# FuzzerFuca.net
KiCad netlist of a schematic drawn in Altium Designer
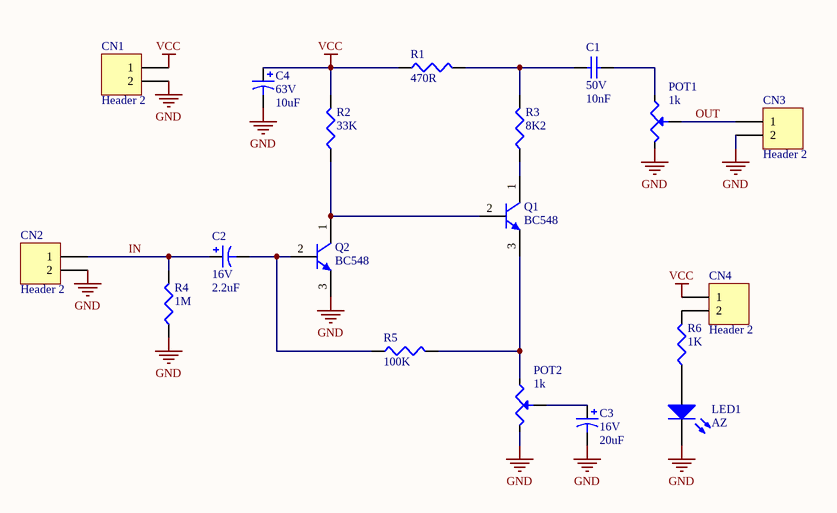
[diagram p0: FuzzerFuca.SchDoc]

(export (version "E")
  (design (tool "Eeschema 10.0.6"))
  (components
    (comp (ref "C1")
      (value "10nF")
      (footprint "CCERAMIC-02I")
      (description "Capacitor (Semiconductor SIM Model)")
      (fields (field (name "TENSÃO") "50V") (field (name "Comment") "Capacitor Cerâmico"))
      (libsource (lib "NavarroCAP") (part "Cap 10nF 50V 0603 X7R 5%"))
    )
    (comp (ref "C2")
      (value "2.2uF")
      (footprint "CPOLRAD5X11")
      (description "Polarized Capacitor")
      (fields (field (name "TENSÃO") "16V") (field (name "Comment") "Capacitor Tântalo"))
      (libsource (lib "NavarroCAP") (part "PCap 2.2uF 16V 1206 LOESR"))
    )
    (comp (ref "C3")
      (value "20uF")
      (footprint "CPOLRAD5X11")
      (description "Polarized Capacitor")
      (fields (field (name "TENSÃO") "16V") (field (name "Comment") "Capacitor Tântalo"))
      (libsource (lib "NavarroCAP") (part "PCap 2.2uF 16V 1206 LOESR"))
    )
    (comp (ref "C4")
      (value "10uF")
      (footprint "CPOLRAD5X11")
      (description "Polarized Capacitor (Radial)")
      (fields (field (name "TENSÃO") "63V") (field (name "Comment") "Capacitor Eletrolítico"))
      (libsource (lib "NavarroCAP") (part "PCap 10uF 63V 5d.x13h"))
    )
    (comp (ref "CN1")
      (value "Header 2")
      (footprint "CONN HDR1X2")
      (description "Header, 2-Pin")
      (libsource (lib "NavarroCON") (part "Header 2"))
    )
    (comp (ref "CN2")
      (value "Header 2")
      (footprint "CONN HDR1X2")
      (description "Header, 2-Pin")
      (libsource (lib "NavarroCON") (part "Header 2"))
    )
    (comp (ref "CN3")
      (value "Header 2")
      (footprint "CONN HDR1X2")
      (description "Header, 2-Pin")
      (libsource (lib "") (part "Header 2_1"))
    )
    (comp (ref "CN4")
      (value "Header 2")
      (footprint "CONN HDR1X2")
      (description "Header, 2-Pin")
      (libsource (lib "") (part "Header 2_1"))
    )
    (comp (ref "LED1")
      (value "AZ")
      (footprint "LED 5MM")
      (description "LED")
      (fields (field (name "Comment") "LED TH 5MM AZ"))
      (libsource (lib "NavarroSEMI") (part "LED TH 5MM AZ"))
    )
    (comp (ref "POT1")
      (value "1k")
      (footprint "POT - GENERICO")
      (description "Potenciometro")
      (fields (field (name "Comment") "Potenciômetro"))
      (libsource (lib "NavarroRES") (part "POT 100k Audio"))
    )
    (comp (ref "POT2")
      (value "1k")
      (footprint "POT - GENERICO")
      (description "Potenciometro")
      (fields (field (name "Comment") "Potenciômetro"))
      (libsource (lib "NavarroRES") (part "POT 100k Audio"))
    )
    (comp (ref "Q1")
      (value "BC548")
      (footprint "TO-92")
      (description "NPN General Purpose Amplifier")
      (libsource (lib "NavarroSEMI") (part "TRS BC548 30V 100mA TO-92"))
    )
    (comp (ref "Q2")
      (value "BC548")
      (footprint "TO-92")
      (description "NPN General Purpose Amplifier")
      (libsource (lib "NavarroSEMI") (part "TRS BC548 30V 100mA TO-92"))
    )
    (comp (ref "R1")
      (value "470R")
      (footprint "Axial 0.125W/H")
      (description "Resistor")
      (libsource (lib "NavarroRES") (part "Res 470R 5% 0603 1/10W"))
    )
    (comp (ref "R2")
      (value "33K")
      (footprint "Axial 0.125W/H")
      (description "Resistor")
      (libsource (lib "NavarroRES") (part "Res 33K 1% 0603 1/10W"))
    )
    (comp (ref "R3")
      (value "8K2")
      (footprint "Axial 0.125W/H")
      (description "Resistor")
      (libsource (lib "NavarroRES") (part "Res 18K2 1% 0603 1/8W"))
    )
    (comp (ref "R4")
      (value "1M")
      (footprint "Axial 0.125W/H")
      (description "Resistor")
      (libsource (lib "NavarroRES") (part "Res 1M 1% 0603 1/10W"))
    )
    (comp (ref "R5")
      (value "100K")
      (footprint "Axial 0.125W/H")
      (description "Resistor")
      (libsource (lib "NavarroRES") (part "Res 100K 1% 0603 1/10W"))
    )
    (comp (ref "R6")
      (value "1K")
      (footprint "Axial 0.125W/H")
      (description "Resistor")
      (libsource (lib "NavarroRES") (part "Res 18K2 1% 0603 1/8W"))
    )
  )
  (nets
    (net (code "1") (name "/IN") (class "Default")
      (node (ref "C2") (pin "1") (pinfunction "1_1") (pintype "passive"))
      (node (ref "CN2") (pin "1") (pinfunction "1_1") (pintype "passive"))
      (node (ref "R4") (pin "2") (pinfunction "2_2") (pintype "passive"))
    )
    (net (code "2") (name "/OUT") (class "Default")
      (node (ref "CN3") (pin "1") (pinfunction "1_1") (pintype "passive"))
      (node (ref "POT1") (pin "2") (pinfunction "TAP_2") (pintype "passive"))
    )
    (net (code "3") (name "GND") (class "Default")
      (node (ref "C3") (pin "2") (pinfunction "2_2") (pintype "passive"))
      (node (ref "C4") (pin "2") (pinfunction "2_2") (pintype "passive"))
      (node (ref "CN1") (pin "2") (pinfunction "2_2") (pintype "passive"))
      (node (ref "CN2") (pin "2") (pinfunction "2_2") (pintype "passive"))
      (node (ref "CN3") (pin "2") (pinfunction "2_2") (pintype "passive"))
      (node (ref "LED1") (pin "2") (pinfunction "K_2") (pintype "passive"))
      (node (ref "POT1") (pin "3") (pinfunction "3_3") (pintype "passive"))
      (node (ref "POT2") (pin "3") (pinfunction "3_3") (pintype "passive"))
      (node (ref "Q2") (pin "3") (pinfunction "E_3") (pintype "passive"))
      (node (ref "R4") (pin "1") (pinfunction "1_1") (pintype "passive"))
    )
    (net (code "4") (name "Net-(C1-Pad1)") (class "Default")
      (node (ref "C1") (pin "1") (pinfunction "1_1") (pintype "passive"))
      (node (ref "R1") (pin "2") (pinfunction "2_2") (pintype "passive"))
      (node (ref "R3") (pin "2") (pinfunction "2_2") (pintype "passive"))
    )
    (net (code "5") (name "Net-(C1-Pad2)") (class "Default")
      (node (ref "C1") (pin "2") (pinfunction "2_2") (pintype "passive"))
      (node (ref "POT1") (pin "1") (pinfunction "1_1") (pintype "passive"))
    )
    (net (code "6") (name "Net-(CN4-Pad2)") (class "Default")
      (node (ref "CN4") (pin "2") (pinfunction "2_2") (pintype "passive"))
      (node (ref "R6") (pin "2") (pinfunction "2_2") (pintype "passive"))
    )
    (net (code "7") (name "Net-(LED1-A)") (class "Default")
      (node (ref "LED1") (pin "1") (pinfunction "A_1") (pintype "passive"))
      (node (ref "R6") (pin "1") (pinfunction "1_1") (pintype "passive"))
    )
    (net (code "8") (name "Net-(POT2-TAP)") (class "Default")
      (node (ref "C3") (pin "1") (pinfunction "1_1") (pintype "passive"))
      (node (ref "POT2") (pin "2") (pinfunction "TAP_2") (pintype "passive"))
    )
    (net (code "9") (name "Net-(Q1-B)") (class "Default")
      (node (ref "Q1") (pin "2") (pinfunction "B_2") (pintype "passive"))
      (node (ref "Q2") (pin "1") (pinfunction "C_1") (pintype "passive"))
      (node (ref "R2") (pin "1") (pinfunction "1_1") (pintype "passive"))
    )
    (net (code "10") (name "Net-(Q1-C)") (class "Default")
      (node (ref "Q1") (pin "1") (pinfunction "C_1") (pintype "passive"))
      (node (ref "R3") (pin "1") (pinfunction "1_1") (pintype "passive"))
    )
    (net (code "11") (name "Net-(Q1-E)") (class "Default")
      (node (ref "POT2") (pin "1") (pinfunction "1_1") (pintype "passive"))
      (node (ref "Q1") (pin "3") (pinfunction "E_3") (pintype "passive"))
      (node (ref "R5") (pin "2") (pinfunction "2_2") (pintype "passive"))
    )
    (net (code "12") (name "Net-(Q2-B)") (class "Default")
      (node (ref "C2") (pin "2") (pinfunction "2_2") (pintype "passive"))
      (node (ref "Q2") (pin "2") (pinfunction "B_2") (pintype "passive"))
      (node (ref "R5") (pin "1") (pinfunction "1_1") (pintype "passive"))
    )
    (net (code "13") (name "VCC") (class "Default")
      (node (ref "C4") (pin "1") (pinfunction "1_1") (pintype "passive"))
      (node (ref "CN1") (pin "1") (pinfunction "1_1") (pintype "passive"))
      (node (ref "CN4") (pin "1") (pinfunction "1_1") (pintype "passive"))
      (node (ref "R1") (pin "1") (pinfunction "1_1") (pintype "passive"))
      (node (ref "R2") (pin "2") (pinfunction "2_2") (pintype "passive"))
    )
  )
)
